# AutoTunerV3.net
KiCad netlist of a schematic drawn in EAGLE
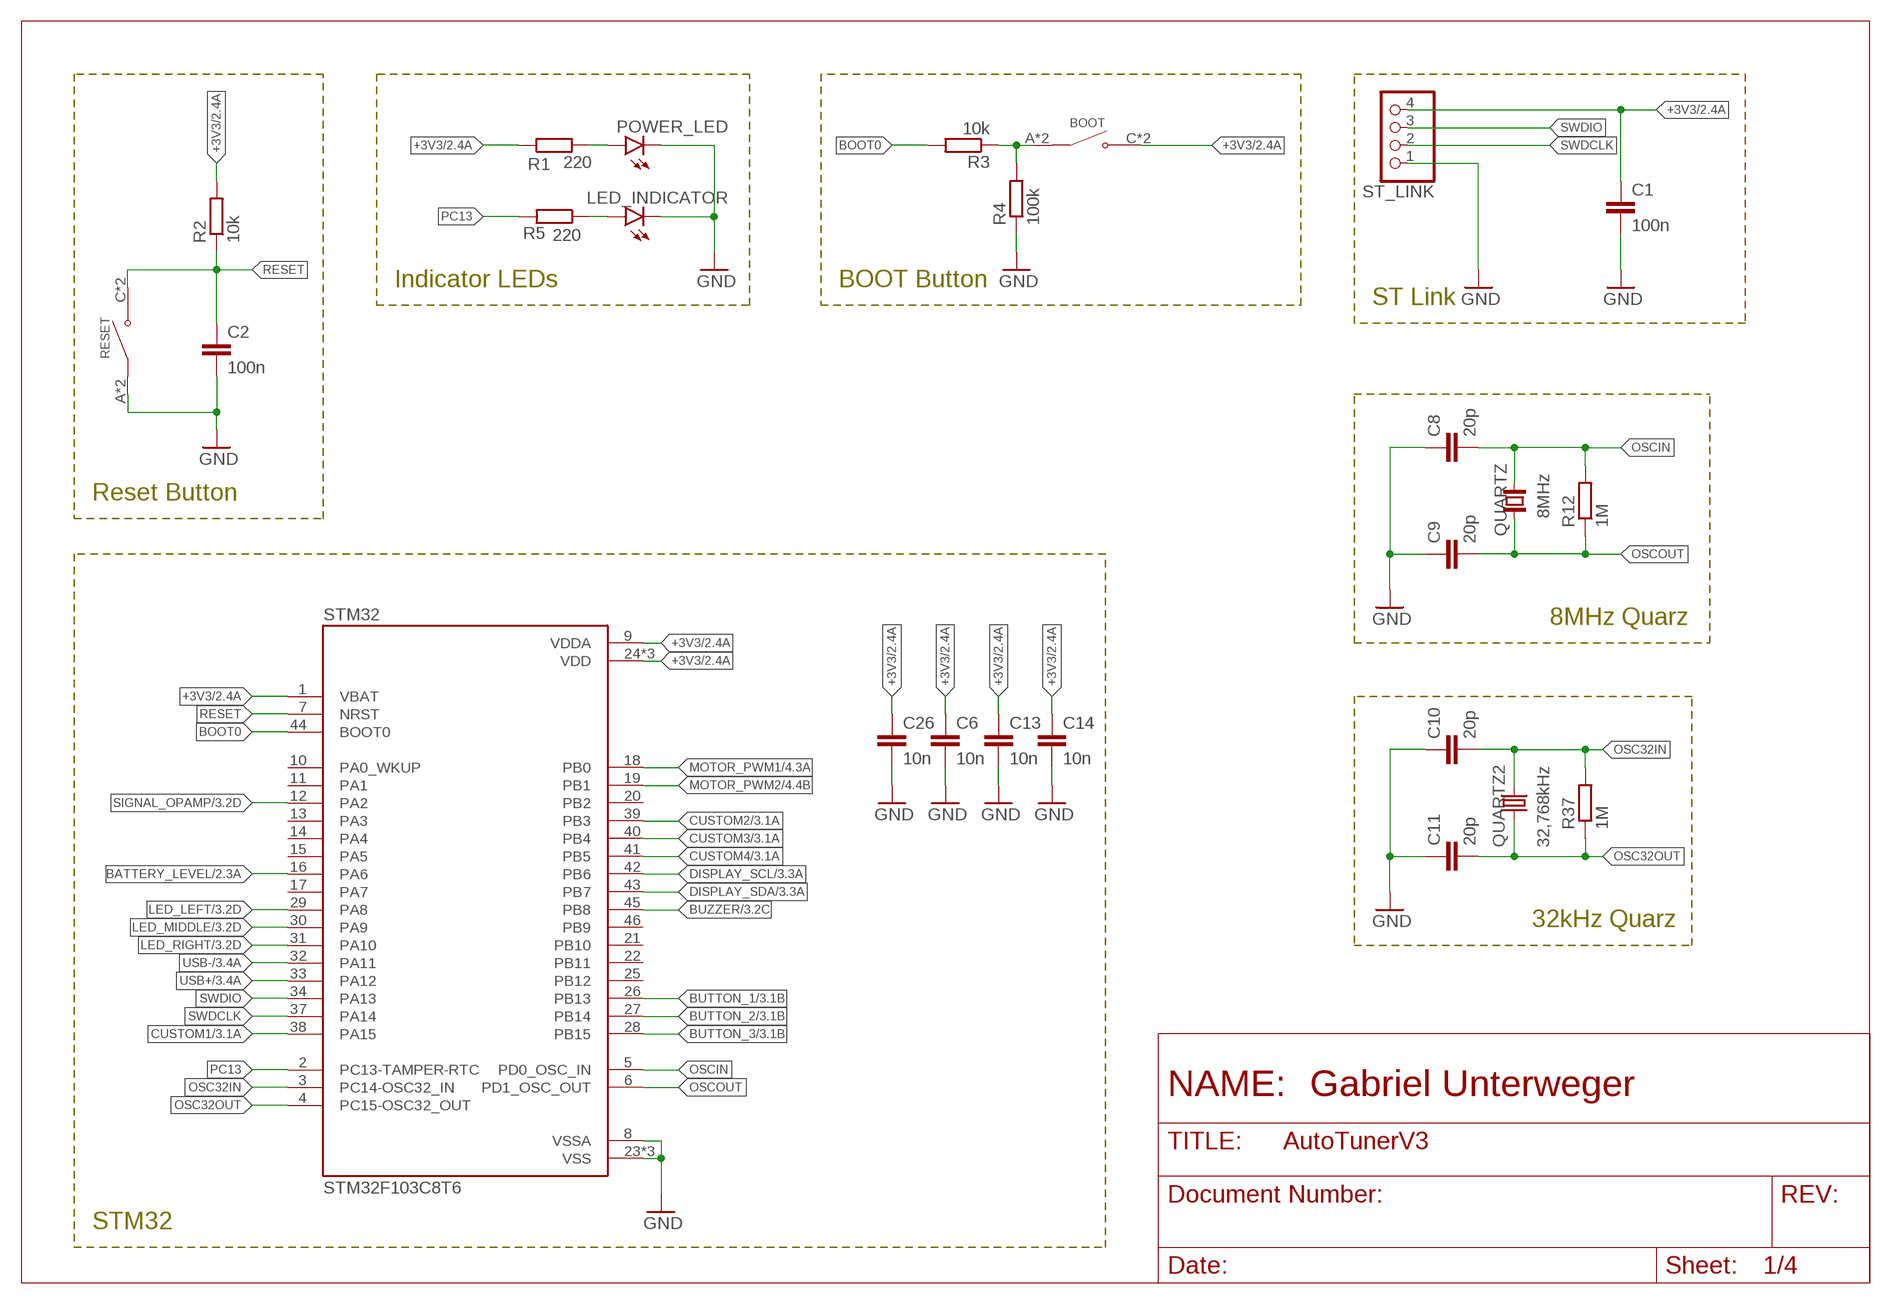
[diagram p0: schematic, sheet 1]
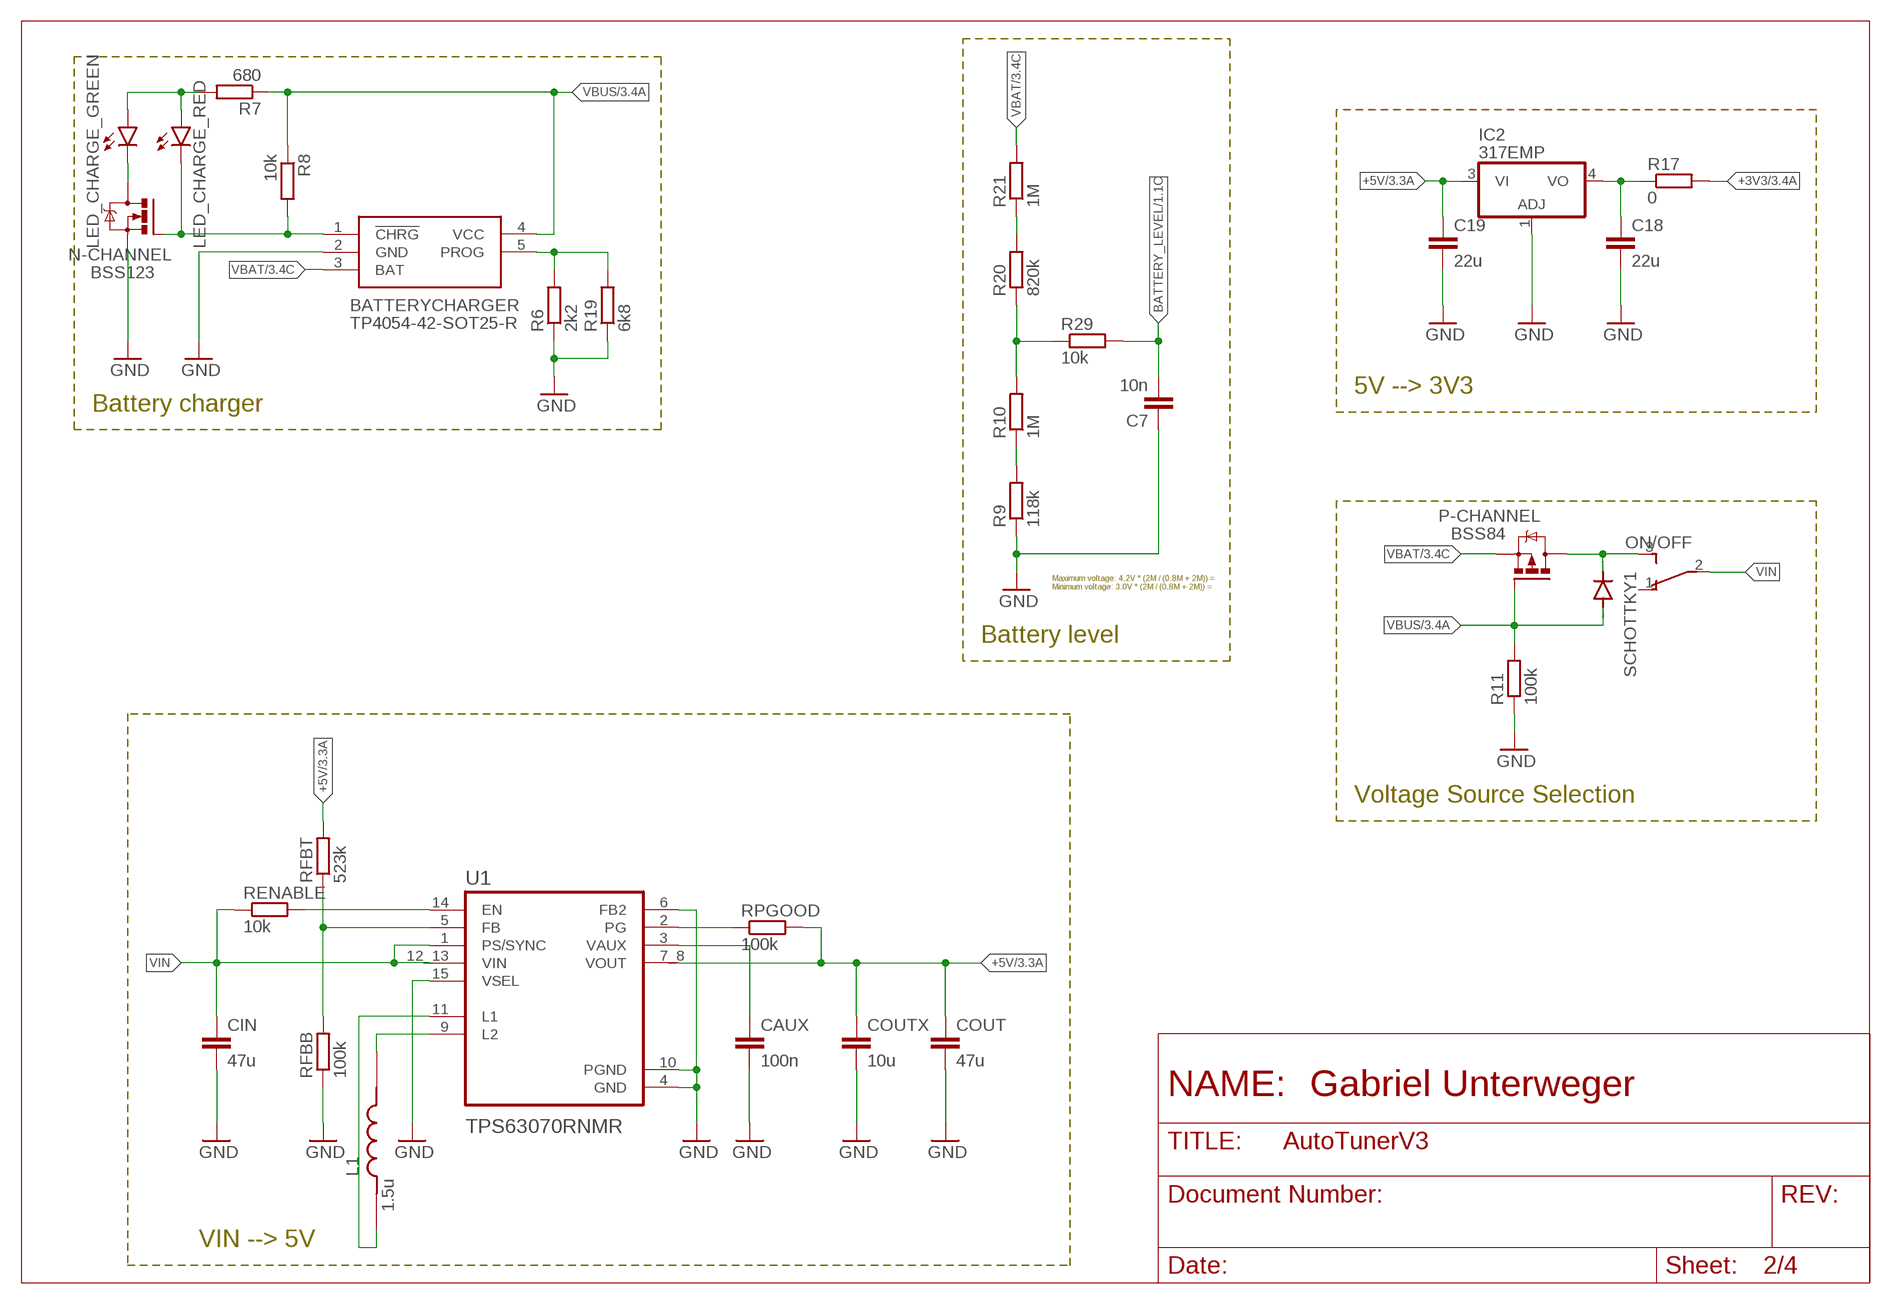
[diagram p1: schematic, sheet 2]
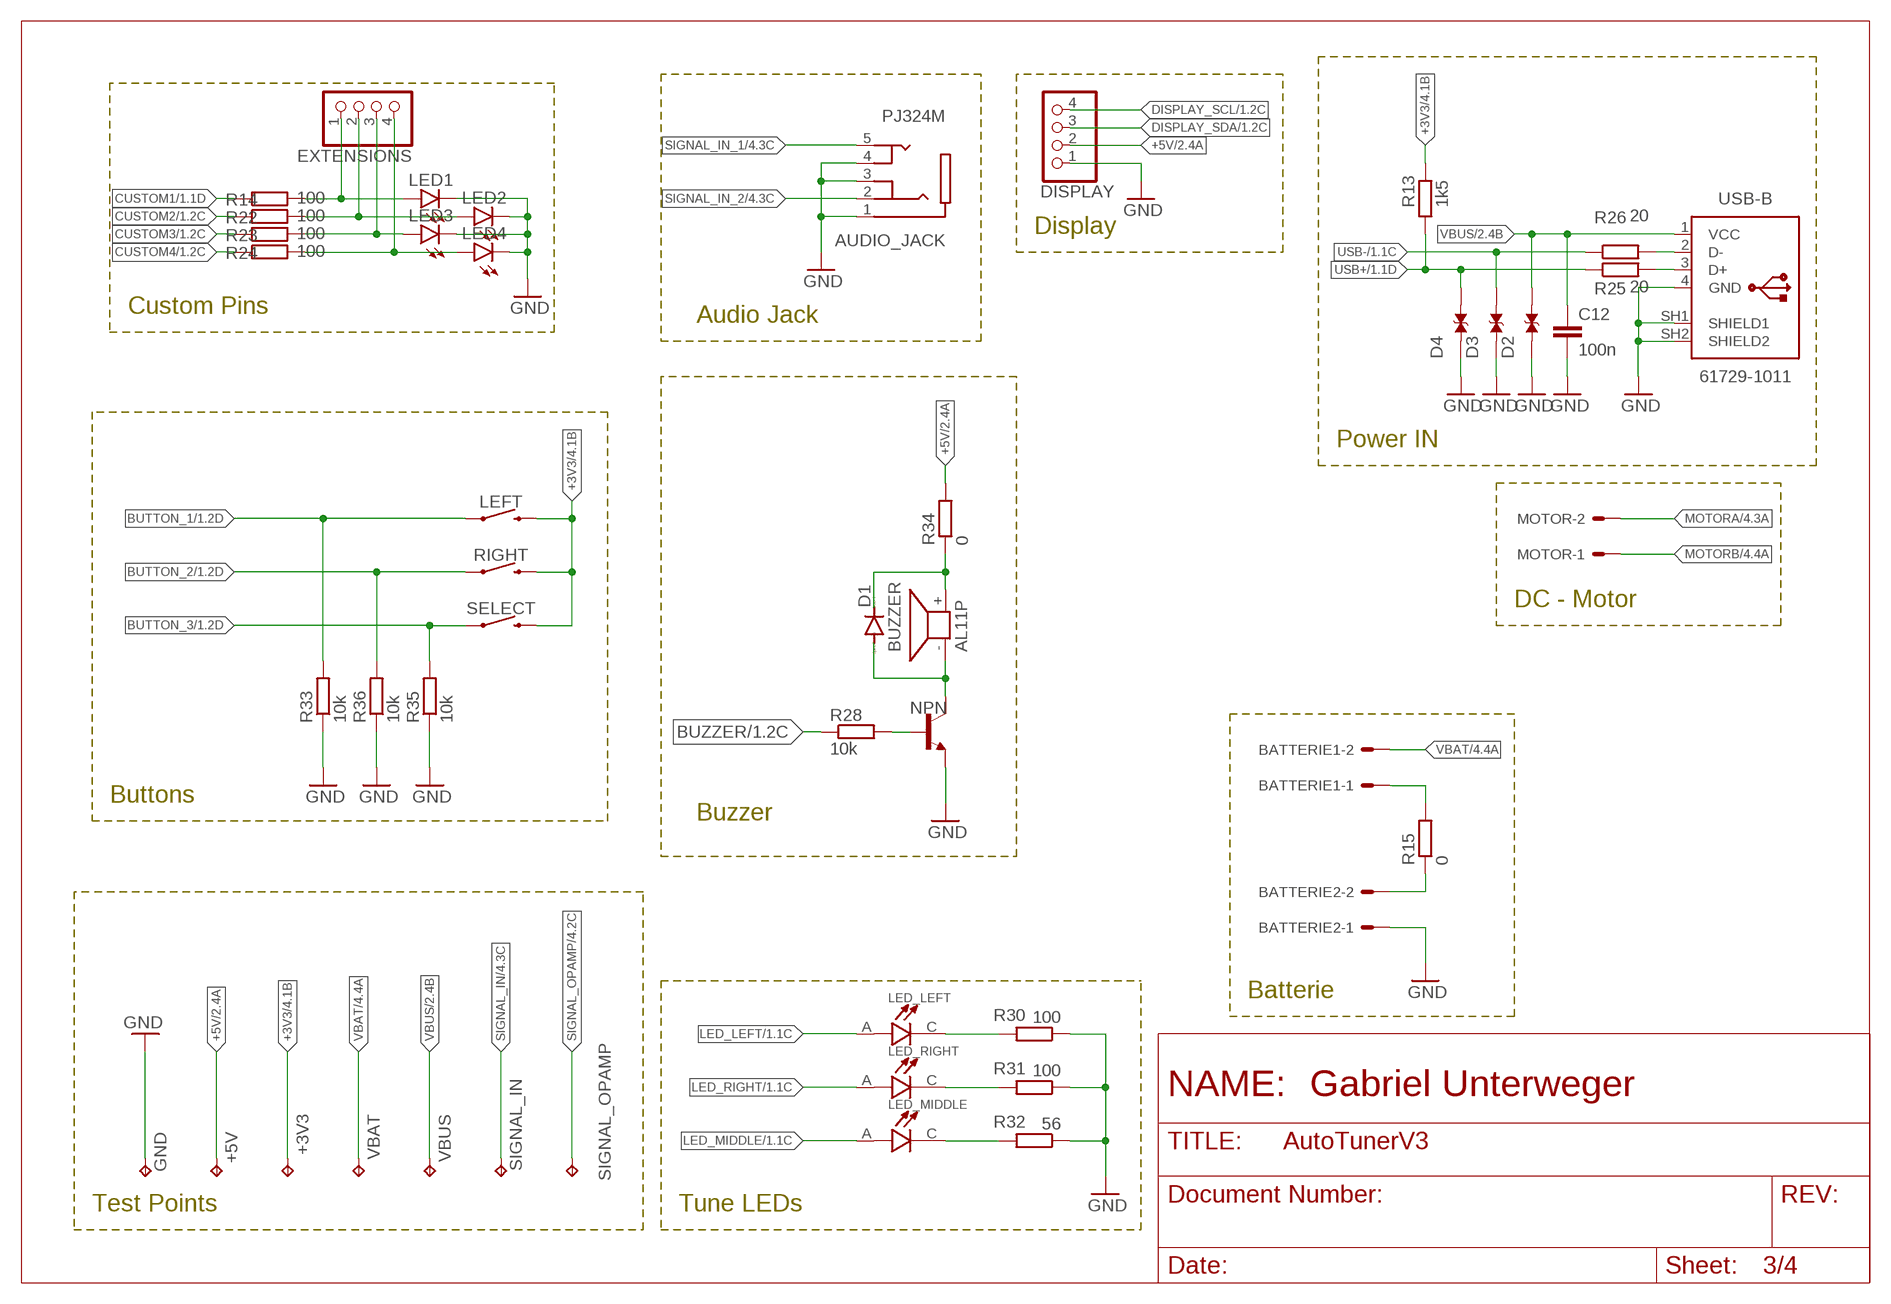
[diagram p2: schematic, sheet 3]
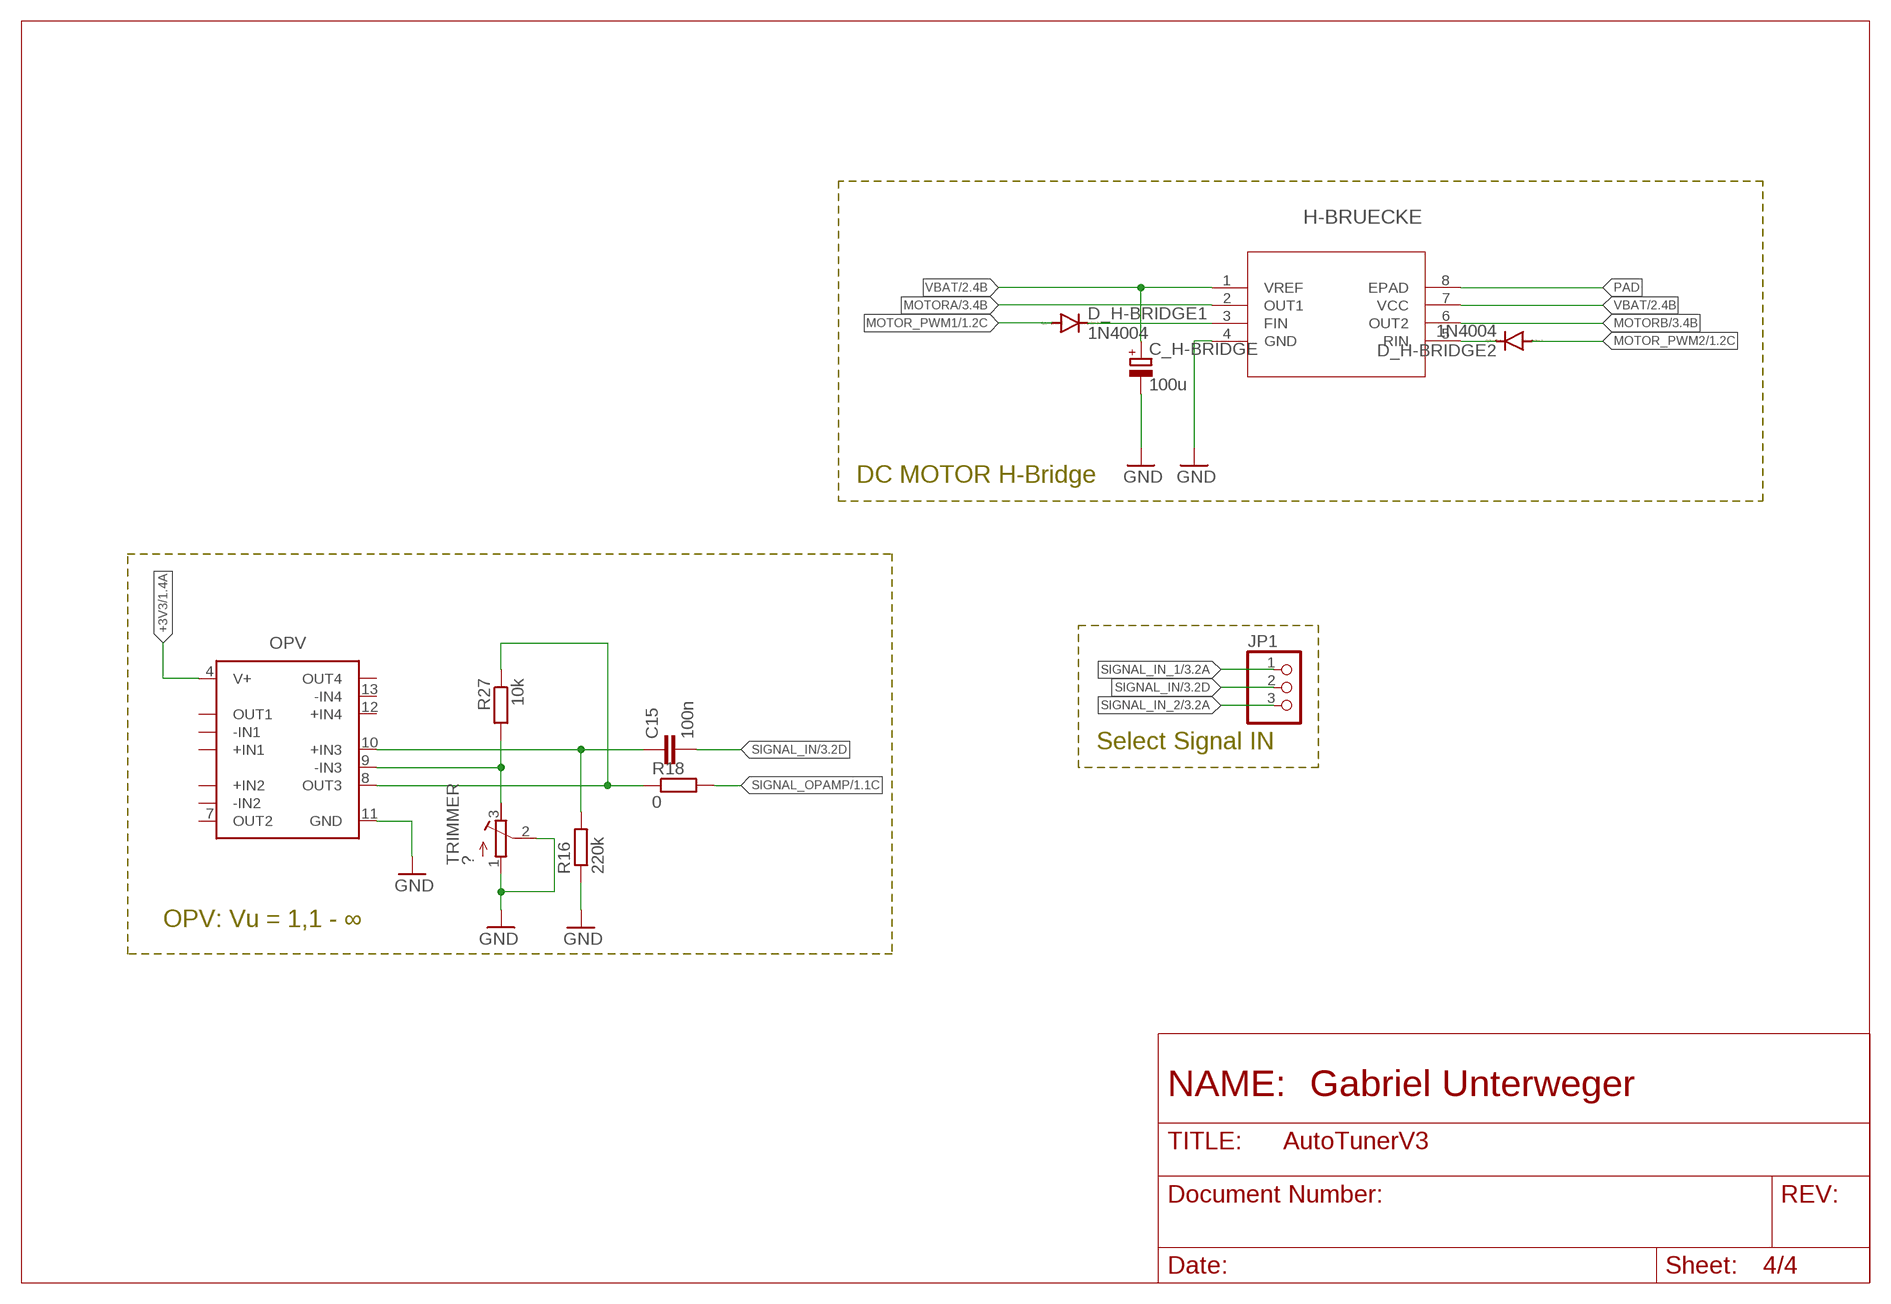
[diagram p3: schematic, sheet 4]

(export (version "E")
  (design (tool "Eeschema 10.0.6"))
  (components
    (comp (ref "+3V3")
      (value "TPB1,27")
      (footprint "eagle-import:B1,27")
      (libsource (lib "eagle-import") (part "TPB1,27"))
    )
    (comp (ref "+5V")
      (value "TPB1,27")
      (footprint "eagle-import:B1,27")
      (libsource (lib "eagle-import") (part "TPB1,27"))
    )
    (comp (ref "AUDIO_JACK")
      (value "PJ324M")
      (footprint "eagle-import:WENZHOU_PJ324M")
      (fields (field (name "MF") "Wenzhou QingPu Electronics Co.Ltd"))
      (libsource (lib "eagle-import") (part "PJ324M"))
    )
    (comp (ref "BATTERIE1")
      (value "22-27-2021-02")
      (footprint "eagle-import:6410-02")
      (fields (field (name "MF") "MOLEX"))
      (libsource (lib "eagle-import") (part "22-?-0227-2021"))
    )
    (comp (ref "BATTERIE2")
      (value "22-27-2021-02")
      (footprint "eagle-import:6410-02")
      (fields (field (name "MF") "MOLEX"))
      (libsource (lib "eagle-import") (part "22-?-0227-2021"))
    )
    (comp (ref "BUZZER")
      (value "AL11P")
      (footprint "eagle-import:AL11P")
      (libsource (lib "eagle-import") (part "AL11P"))
    )
    (comp (ref "C12")
      (value "100n")
      (footprint "eagle-import:C0805")
      (libsource (lib "eagle-import") (part "C-EUC0805"))
    )
    (comp (ref "D1")
      (value "DIODE-SOD323-R")
      (footprint "eagle-import:SOD323-R")
      (fields (field (name "LCSC_PART") "C2128"))
      (libsource (lib "eagle-import") (part "DIODE-SOD323-R"))
    )
    (comp (ref "D2")
      (value "TESD5V0L1UC_RJG")
      (footprint "eagle-import:DIO_TESD5V0L1UC_RJG")
      (fields
        (field (name "MF") "Taiwan Semiconductor Corporation")
        (field (name "MP") "TESD5V0L1UC RJG")
        (field (name "LCSC_PART") "C7420372")
      )
      (libsource (lib "eagle-import") (part "TESD5V0L1UC_RJG"))
    )
    (comp (ref "D3")
      (value "TESD5V0L1UC_RJG")
      (footprint "eagle-import:DIO_TESD5V0L1UC_RJG")
      (fields
        (field (name "MF") "Taiwan Semiconductor Corporation")
        (field (name "MP") "TESD5V0L1UC RJG")
        (field (name "LCSC_PART") "C7420372")
      )
      (libsource (lib "eagle-import") (part "TESD5V0L1UC_RJG"))
    )
    (comp (ref "D4")
      (value "TESD5V0L1UC_RJG")
      (footprint "eagle-import:DIO_TESD5V0L1UC_RJG")
      (fields
        (field (name "MF") "Taiwan Semiconductor Corporation")
        (field (name "MP") "TESD5V0L1UC RJG")
        (field (name "LCSC_PART") "C7420372")
      )
      (libsource (lib "eagle-import") (part "TESD5V0L1UC_RJG"))
    )
    (comp (ref "DISPLAY")
      (value "PINHD-1X4")
      (footprint "eagle-import:1X04")
      (libsource (lib "eagle-import") (part "PINHD-1X4"))
    )
    (comp (ref "EXTENSIONS")
      (value "PINHD-1X4/90")
      (footprint "eagle-import:1X04_90")
      (libsource (lib "eagle-import") (part "PINHD-1X4/90"))
    )
    (comp (ref "GND")
      (value "TPB1,27")
      (footprint "eagle-import:B1,27")
      (libsource (lib "eagle-import") (part "TPB1,27"))
    )
    (comp (ref "LED1")
      (value "LEDCHIP-LED0805")
      (footprint "eagle-import:CHIP-LED0805")
      (fields (field (name "LCSC_PART") "C2297"))
      (libsource (lib "eagle-import") (part "LEDCHIP-LED0805"))
    )
    (comp (ref "LED2")
      (value "LEDCHIP-LED0805")
      (footprint "eagle-import:CHIP-LED0805")
      (fields (field (name "LCSC_PART") "C2297"))
      (libsource (lib "eagle-import") (part "LEDCHIP-LED0805"))
    )
    (comp (ref "LED3")
      (value "LEDCHIP-LED0805")
      (footprint "eagle-import:CHIP-LED0805")
      (fields (field (name "LCSC_PART") "C2297"))
      (libsource (lib "eagle-import") (part "LEDCHIP-LED0805"))
    )
    (comp (ref "LED4")
      (value "LEDCHIP-LED0805")
      (footprint "eagle-import:CHIP-LED0805")
      (fields (field (name "LCSC_PART") "C2297"))
      (libsource (lib "eagle-import") (part "LEDCHIP-LED0805"))
    )
    (comp (ref "LED_LEFT")
      (value "L-53GD")
      (footprint "eagle-import:LEDRD254W50D500H1060")
      (fields (field (name "MF") "Kingbright"))
      (libsource (lib "eagle-import") (part "L-53GD"))
    )
    (comp (ref "LED_MIDDLE")
      (value "L-53GD")
      (footprint "eagle-import:LEDRD254W50D500H1060")
      (fields (field (name "MF") "Kingbright"))
      (libsource (lib "eagle-import") (part "L-53GD"))
    )
    (comp (ref "LED_RIGHT")
      (value "L-53GD")
      (footprint "eagle-import:LEDRD254W50D500H1060")
      (fields (field (name "MF") "Kingbright"))
      (libsource (lib "eagle-import") (part "L-53GD"))
    )
    (comp (ref "LEFT")
      (value "MOMENTARY-SWITCH-SPST-PTH-12MM")
      (footprint "eagle-import:TACTILE_SWITCH_PTH_12MM")
      (libsource (lib "eagle-import") (part "MOMENTARY-SWITCH-SPST-PTH-12MM"))
    )
    (comp (ref "MOTOR")
      (value "22-27-2021-02")
      (footprint "eagle-import:6410-02")
      (fields (field (name "MF") "MOLEX"))
      (libsource (lib "eagle-import") (part "22-?-0227-2021"))
    )
    (comp (ref "NPN")
      (value "-NPN-SOT23-EBC")
      (footprint "eagle-import:SOT23-EBC")
      (fields (field (name "LCSC_PART") "C364312"))
      (libsource (lib "eagle-import") (part "-NPN-SOT23-EBC"))
    )
    (comp (ref "R13")
      (value "1k5")
      (footprint "eagle-import:R0805")
      (libsource (lib "eagle-import") (part "R-EU_R0805"))
    )
    (comp (ref "R14")
      (value "100")
      (footprint "eagle-import:R0805")
      (libsource (lib "eagle-import") (part "R-EU_R0805"))
    )
    (comp (ref "R15")
      (value "0")
      (footprint "eagle-import:R0805")
      (libsource (lib "eagle-import") (part "R-EU_R0805"))
    )
    (comp (ref "R22")
      (value "100")
      (footprint "eagle-import:R0805")
      (libsource (lib "eagle-import") (part "R-EU_R0805"))
    )
    (comp (ref "R23")
      (value "100")
      (footprint "eagle-import:R0805")
      (libsource (lib "eagle-import") (part "R-EU_R0805"))
    )
    (comp (ref "R24")
      (value "100")
      (footprint "eagle-import:R0805")
      (libsource (lib "eagle-import") (part "R-EU_R0805"))
    )
    (comp (ref "R25")
      (value "20")
      (footprint "eagle-import:R0805")
      (libsource (lib "eagle-import") (part "R-EU_R0805"))
    )
    (comp (ref "R26")
      (value "20")
      (footprint "eagle-import:R0805")
      (libsource (lib "eagle-import") (part "R-EU_R0805"))
    )
    (comp (ref "R28")
      (value "10k")
      (footprint "eagle-import:R0805")
      (libsource (lib "eagle-import") (part "R-EU_R0805"))
    )
    (comp (ref "R30")
      (value "100")
      (footprint "eagle-import:R0805")
      (libsource (lib "eagle-import") (part "R-EU_R0805"))
    )
    (comp (ref "R31")
      (value "100")
      (footprint "eagle-import:R0805")
      (libsource (lib "eagle-import") (part "R-EU_R0805"))
    )
    (comp (ref "R32")
      (value "56")
      (footprint "eagle-import:R0805")
      (libsource (lib "eagle-import") (part "R-EU_R0805"))
    )
    (comp (ref "R33")
      (value "10k")
      (footprint "eagle-import:R0805")
      (libsource (lib "eagle-import") (part "R-EU_R0805"))
    )
    (comp (ref "R34")
      (value "0")
      (footprint "eagle-import:R0805")
      (libsource (lib "eagle-import") (part "R-EU_R0805"))
    )
    (comp (ref "R35")
      (value "10k")
      (footprint "eagle-import:R0805")
      (libsource (lib "eagle-import") (part "R-EU_R0805"))
    )
    (comp (ref "R36")
      (value "10k")
      (footprint "eagle-import:R0805")
      (libsource (lib "eagle-import") (part "R-EU_R0805"))
    )
    (comp (ref "RIGHT")
      (value "MOMENTARY-SWITCH-SPST-PTH-12MM")
      (footprint "eagle-import:TACTILE_SWITCH_PTH_12MM")
      (libsource (lib "eagle-import") (part "MOMENTARY-SWITCH-SPST-PTH-12MM"))
    )
    (comp (ref "SELECT")
      (value "MOMENTARY-SWITCH-SPST-PTH-12MM")
      (footprint "eagle-import:TACTILE_SWITCH_PTH_12MM")
      (libsource (lib "eagle-import") (part "MOMENTARY-SWITCH-SPST-PTH-12MM"))
    )
    (comp (ref "SIGNAL_IN")
      (value "TPB1,27")
      (footprint "eagle-import:B1,27")
      (libsource (lib "eagle-import") (part "TPB1,27"))
    )
    (comp (ref "SIGNAL_OPAMP")
      (value "TPB1,27")
      (footprint "eagle-import:B1,27")
      (libsource (lib "eagle-import") (part "TPB1,27"))
    )
    (comp (ref "USB-B")
      (value "61729-1011")
      (footprint "eagle-import:61729-1011BLF")
      (fields (field (name "MANUFACTURER") "Amphenol ICC (FCI)") (field (name "MPN") "61729-1011BLF"))
      (libsource (lib "eagle-import") (part "61729-1011"))
    )
    (comp (ref "VBAT")
      (value "TPB1,27")
      (footprint "eagle-import:B1,27")
      (libsource (lib "eagle-import") (part "TPB1,27"))
    )
    (comp (ref "VBUS")
      (value "TPB1,27")
      (footprint "eagle-import:B1,27")
      (libsource (lib "eagle-import") (part "TPB1,27"))
    )
    (comp (ref "BOOT")
      (value "TS-1187A-B-A-B")
      (footprint "eagle-import:SW_TS-1187A-B-A-B")
      (fields (field (name "MF") "XKB Industrial Precision") (field (name "LCSC_PART") "C318884"))
      (libsource (lib "eagle-import") (part "TS-1187A-B-A-B"))
    )
    (comp (ref "C1")
      (value "100n")
      (footprint "eagle-import:C0805")
      (libsource (lib "eagle-import") (part "C-EUC0805"))
    )
    (comp (ref "C2")
      (value "100n")
      (footprint "eagle-import:C0805")
      (libsource (lib "eagle-import") (part "C-EUC0805"))
    )
    (comp (ref "C6")
      (value "10n")
      (footprint "eagle-import:C0805")
      (libsource (lib "eagle-import") (part "C-EUC0805"))
    )
    (comp (ref "C8")
      (value "20p")
      (footprint "eagle-import:C0805")
      (libsource (lib "eagle-import") (part "C-EUC0805"))
    )
    (comp (ref "C9")
      (value "20p")
      (footprint "eagle-import:C0805")
      (libsource (lib "eagle-import") (part "C-EUC0805"))
    )
    (comp (ref "C10")
      (value "20p")
      (footprint "eagle-import:C0805")
      (libsource (lib "eagle-import") (part "C-EUC0805"))
    )
    (comp (ref "C11")
      (value "20p")
      (footprint "eagle-import:C0805")
      (libsource (lib "eagle-import") (part "C-EUC0805"))
    )
    (comp (ref "C13")
      (value "10n")
      (footprint "eagle-import:C0805")
      (libsource (lib "eagle-import") (part "C-EUC0805"))
    )
    (comp (ref "C14")
      (value "10n")
      (footprint "eagle-import:C0805")
      (libsource (lib "eagle-import") (part "C-EUC0805"))
    )
    (comp (ref "C26")
      (value "10n")
      (footprint "eagle-import:C0805")
      (libsource (lib "eagle-import") (part "C-EUC0805"))
    )
    (comp (ref "LED_INDICATOR")
      (value "LEDCHIPLED_0805")
      (footprint "eagle-import:CHIPLED_0805")
      (fields (field (name "LCSC_PART") "C2296"))
      (libsource (lib "eagle-import") (part "LEDCHIPLED_0805"))
    )
    (comp (ref "POWER_LED")
      (value "LEDCHIPLED_0805")
      (footprint "eagle-import:CHIPLED_0805")
      (fields (field (name "LCSC_PART") "C2297"))
      (libsource (lib "eagle-import") (part "LEDCHIPLED_0805"))
    )
    (comp (ref "QUARTZ")
      (value "8MHz")
      (footprint "eagle-import:CRYSTAL_2-SMD-5X3")
      (fields (field (name "LCSC_PART") "C115962"))
      (libsource (lib "eagle-import") (part "CRYSTAL_NX5032GA"))
    )
    (comp (ref "QUARTZ2")
      (value "32,768kHz")
      (footprint "eagle-import:3.2X1.5")
      (fields (field (name "LCSC_PART") "C32346"))
      (libsource (lib "eagle-import") (part "KX-327-NHF"))
    )
    (comp (ref "R1")
      (value "220")
      (footprint "eagle-import:R0805")
      (fields (field (name "LCSC_PART") "C17557"))
      (libsource (lib "eagle-import") (part "R-EU_R0805"))
    )
    (comp (ref "R2")
      (value "10k")
      (footprint "eagle-import:R0805")
      (libsource (lib "eagle-import") (part "R-EU_R0805"))
    )
    (comp (ref "R3")
      (value "10k")
      (footprint "eagle-import:R0805")
      (libsource (lib "eagle-import") (part "R-EU_R0805"))
    )
    (comp (ref "R4")
      (value "100k")
      (footprint "eagle-import:R0805")
      (libsource (lib "eagle-import") (part "R-EU_R0805"))
    )
    (comp (ref "R5")
      (value "220")
      (footprint "eagle-import:R0805")
      (fields (field (name "LCSC_PART") "C17802"))
      (libsource (lib "eagle-import") (part "R-EU_R0805"))
    )
    (comp (ref "R12")
      (value "1M")
      (footprint "eagle-import:R0805")
      (libsource (lib "eagle-import") (part "R-EU_R0805"))
    )
    (comp (ref "R37")
      (value "1M")
      (footprint "eagle-import:R0805")
      (libsource (lib "eagle-import") (part "R-EU_R0805"))
    )
    (comp (ref "RESET")
      (value "TS-1187A-B-A-B")
      (footprint "eagle-import:SW_TS-1187A-B-A-B")
      (fields (field (name "MF") "XKB Industrial Precision") (field (name "LCSC_PART") "C318884"))
      (libsource (lib "eagle-import") (part "TS-1187A-B-A-B"))
    )
    (comp (ref "STM32")
      (value "STM32F103C8T6")
      (footprint "eagle-import:QFP50P900X900X160-48N")
      (fields (field (name "MF") "STMicroelectronics") (field (name "LCSC_PART") "C8734"))
      (libsource (lib "eagle-import") (part "STM32F103C8T6"))
    )
    (comp (ref "ST_LINK")
      (value "PINHD-1X4/90")
      (footprint "eagle-import:1X04_90")
      (libsource (lib "eagle-import") (part "PINHD-1X4/90"))
    )
    (comp (ref "BATTERYCHARGER")
      (value "TP4054-42-SOT25-R")
      (footprint "eagle-import:SOT95P280X100-5N")
      (fields (field (name "LCSC_PART") "C32574"))
      (libsource (lib "eagle-import") (part "TP4054-42-SOT25-R"))
    )
    (comp (ref "C7")
      (value "10n")
      (footprint "eagle-import:C0805")
      (libsource (lib "eagle-import") (part "C-EUC0805"))
    )
    (comp (ref "C18")
      (value "22u")
      (footprint "eagle-import:C1206")
      (fields (field (name "LCSC_PART") "C12891"))
      (libsource (lib "eagle-import") (part "C-EUC1206"))
    )
    (comp (ref "C19")
      (value "22u")
      (footprint "eagle-import:C1206")
      (fields (field (name "LCSC_PART") "C12891"))
      (libsource (lib "eagle-import") (part "C-EUC1206"))
    )
    (comp (ref "CAUX")
      (value "100n")
      (footprint "eagle-import:C0402")
      (fields (field (name "LCSC_PART") "C1525"))
      (libsource (lib "eagle-import") (part "C-EUC0402"))
    )
    (comp (ref "CIN")
      (value "47u")
      (footprint "eagle-import:C1206")
      (fields (field (name "LCSC_PART") "C96123"))
      (libsource (lib "eagle-import") (part "C-EUC1206"))
    )
    (comp (ref "COUT")
      (value "47u")
      (footprint "eagle-import:C1206")
      (fields (field (name "LCSC_PART") "C96123"))
      (libsource (lib "eagle-import") (part "C-EUC1206"))
    )
    (comp (ref "COUTX")
      (value "10u")
      (footprint "eagle-import:C0603")
      (fields (field (name "LCSC_PART") "C19702"))
      (libsource (lib "eagle-import") (part "C-EUC0603"))
    )
    (comp (ref "IC2")
      (value "317EMP")
      (footprint "eagle-import:SOT223")
      (fields (field (name "LCSC_PART") "C6186"))
      (libsource (lib "eagle-import") (part "317EMP"))
    )
    (comp (ref "L1")
      (value "1.5u")
      (footprint "eagle-import:IND_XFL4020-152MEC")
      (fields
        (field (name "MF") "Coilcraft")
        (field (name "MP") "XFL4020-152MEC")
        (field (name "LCSC_PART") "C3033018")
      )
      (libsource (lib "eagle-import") (part "XFL4020-152MEC"))
    )
    (comp (ref "LED_CHARGE_GREEN")
      (value "LEDCHIPLED_0805")
      (footprint "eagle-import:CHIPLED_0805")
      (fields (field (name "LCSC_PART") "C2297"))
      (libsource (lib "eagle-import") (part "LEDCHIPLED_0805"))
    )
    (comp (ref "LED_CHARGE_RED")
      (value "LEDCHIPLED_0805")
      (footprint "eagle-import:CHIPLED_0805")
      (fields (field (name "LCSC_PART") "C84256"))
      (libsource (lib "eagle-import") (part "LEDCHIPLED_0805"))
    )
    (comp (ref "N-CHANNEL")
      (value "BSS123")
      (footprint "eagle-import:SOT23")
      (fields
        (field (name "MANUFACTURER") "ON Semiconductor")
        (field (name "MPN") "BSS123L")
        (field (name "LCSC_PART") "C20917")
      )
      (libsource (lib "eagle-import") (part "NMOSFET__SOT23-GSDBSS123"))
    )
    (comp (ref "ON/OFF")
      (value "TL36PO")
      (footprint "eagle-import:TL3XPO")
      (libsource (lib "eagle-import") (part "TL36PO"))
    )
    (comp (ref "P-CHANNEL")
      (value "BSS84")
      (footprint "eagle-import:SOT23")
      (fields (field (name "MANUFACTURER") "ON Semiconductor"))
      (libsource (lib "eagle-import") (part "PMOSFET__SOT23-GSDBSS84"))
    )
    (comp (ref "R6")
      (value "2k2")
      (footprint "eagle-import:R0805")
      (libsource (lib "eagle-import") (part "R-EU_R0805"))
    )
    (comp (ref "R7")
      (value "680")
      (footprint "eagle-import:R0805")
      (libsource (lib "eagle-import") (part "R-EU_R0805"))
    )
    (comp (ref "R8")
      (value "10k")
      (footprint "eagle-import:R0805")
      (libsource (lib "eagle-import") (part "R-EU_R0805"))
    )
    (comp (ref "R9")
      (value "118k")
      (footprint "eagle-import:R0805")
      (libsource (lib "eagle-import") (part "R-EU_R0805"))
    )
    (comp (ref "R10")
      (value "1M")
      (footprint "eagle-import:R0805")
      (libsource (lib "eagle-import") (part "R-EU_R0805"))
    )
    (comp (ref "R11")
      (value "100k")
      (footprint "eagle-import:R0805")
      (libsource (lib "eagle-import") (part "R-EU_R0805"))
    )
    (comp (ref "R17")
      (value "0")
      (footprint "eagle-import:R0805")
      (libsource (lib "eagle-import") (part "R-EU_R0805"))
    )
    (comp (ref "R19")
      (value "6k8")
      (footprint "eagle-import:R0805")
      (libsource (lib "eagle-import") (part "R-EU_R0805"))
    )
    (comp (ref "R20")
      (value "820k")
      (footprint "eagle-import:R0805")
      (libsource (lib "eagle-import") (part "R-EU_R0805"))
    )
    (comp (ref "R21")
      (value "1M")
      (footprint "eagle-import:R0805")
      (libsource (lib "eagle-import") (part "R-EU_R0805"))
    )
    (comp (ref "R29")
      (value "10k")
      (footprint "eagle-import:R0805")
      (libsource (lib "eagle-import") (part "R-EU_R0805"))
    )
    (comp (ref "RENABLE")
      (value "10k")
      (footprint "eagle-import:R0805")
      (libsource (lib "eagle-import") (part "R-EU_R0805"))
    )
    (comp (ref "RFBB")
      (value "100k")
      (footprint "eagle-import:R0805")
      (libsource (lib "eagle-import") (part "R-EU_R0805"))
    )
    (comp (ref "RFBT")
      (value "523k")
      (footprint "eagle-import:R0805")
      (libsource (lib "eagle-import") (part "R-EU_R0805"))
    )
    (comp (ref "RPGOOD")
      (value "100k")
      (footprint "eagle-import:R0805")
      (libsource (lib "eagle-import") (part "R-EU_R0805"))
    )
    (comp (ref "SCHOTTKY1")
      (value "DIODE-SOD323-R")
      (footprint "eagle-import:SOD323-R")
      (fields (field (name "LCSC_PART") "C191023"))
      (libsource (lib "eagle-import") (part "DIODE-SOD323-R"))
    )
    (comp (ref "U1")
      (value "TPS63070RNMR")
      (footprint "eagle-import:VREG_TPS63070RNMR")
      (fields (field (name "MF") "Texas Instruments") (field (name "LCSC_PART") "C109322"))
      (libsource (lib "eagle-import") (part "TPS63070RNMR"))
    )
    (comp (ref "C15")
      (value "100n")
      (footprint "eagle-import:C0805")
      (libsource (lib "eagle-import") (part "C-EUC0805"))
    )
    (comp (ref "C_H-BRIDGE")
      (value "100u")
      (footprint "eagle-import:E2,5-6E")
      (libsource (lib "eagle-import") (part "CPOL-EUE2,5-6E"))
    )
    (comp (ref "D_H-BRIDGE1")
      (value "1N4004")
      (footprint "eagle-import:DO41-10")
      (libsource (lib "eagle-import") (part "1N4004"))
    )
    (comp (ref "D_H-BRIDGE2")
      (value "1N4004")
      (footprint "eagle-import:DO41-10")
      (libsource (lib "eagle-import") (part "1N4004"))
    )
    (comp (ref "H-BRUECKE")
      (value "BD6222HFP-TRHRP7_ROM-M")
      (footprint "eagle-import:HRP7_ROM-M")
      (fields
        (field (name "MANUFACTURER_PART_NUMBER") "BD6222HFP-TR")
        (field (name "COPYRIGHT") "Copyright (C) 2022 Ultra Librarian. All rights reserved.")
      )
      (libsource (lib "eagle-import") (part "BD6222HFP-TRHRP7_ROM-M"))
    )
    (comp (ref "JP1")
      (value "PINHD-1X3")
      (footprint "eagle-import:1X03")
      (libsource (lib "eagle-import") (part "PINHD-1X3"))
    )
    (comp (ref "OPV")
      (value "LM324_SOIC")
      (footprint "eagle-import:SOIC127P600X175-14N")
      (fields (field (name "MANUFACTURER") "Generic") (field (name "LCSC_PART") "C71035"))
      (libsource (lib "eagle-import") (part "LM324_SOIC"))
    )
    (comp (ref "R16")
      (value "220k")
      (footprint "eagle-import:R0805")
      (libsource (lib "eagle-import") (part "R-EU_R0805"))
    )
    (comp (ref "R18")
      (value "0")
      (footprint "eagle-import:R0805")
      (libsource (lib "eagle-import") (part "R-EU_R0805"))
    )
    (comp (ref "R27")
      (value "10k")
      (footprint "eagle-import:R0805")
      (libsource (lib "eagle-import") (part "R-EU_R0805"))
    )
    (comp (ref "TRIMMER")
      (value "?")
      (footprint "eagle-import:RTRIM3339P")
      (libsource (lib "eagle-import") (part "R-TRIMM3339P"))
    )
  )
  (nets
    (net (code "1") (name "+3V3") (class "Default")
      (node (ref "+3V3") (pin "TP") (pinfunction "TP_TP") (pintype "input"))
      (node (ref "BOOT") (pin "C") (pinfunction "NO_C") (pintype "passive"))
      (node (ref "BOOT") (pin "D") (pinfunction "NO_D") (pintype "passive"))
      (node (ref "C1") (pin "1") (pinfunction "1_1") (pintype "passive"))
      (node (ref "C13") (pin "1") (pinfunction "1_1") (pintype "passive"))
      (node (ref "C14") (pin "1") (pinfunction "1_1") (pintype "passive"))
      (node (ref "C26") (pin "1") (pinfunction "1_1") (pintype "passive"))
      (node (ref "C6") (pin "1") (pinfunction "1_1") (pintype "passive"))
      (node (ref "LEFT") (pin "3") (pinfunction "2_3") (pintype "passive"))
      (node (ref "OPV") (pin "4") (pinfunction "V+_4") (pintype "passive"))
      (node (ref "R1") (pin "1") (pinfunction "1_1") (pintype "passive"))
      (node (ref "R13") (pin "2") (pinfunction "2_2") (pintype "passive"))
      (node (ref "R17") (pin "2") (pinfunction "2_2") (pintype "passive"))
      (node (ref "R2") (pin "2") (pinfunction "2_2") (pintype "passive"))
      (node (ref "RIGHT") (pin "3") (pinfunction "2_3") (pintype "passive"))
      (node (ref "SELECT") (pin "3") (pinfunction "2_3") (pintype "passive"))
      (node (ref "STM32") (pin "1") (pinfunction "VBAT_1") (pintype "bidirectional"))
      (node (ref "STM32") (pin "24") (pinfunction "VDD_24") (pintype "power_in"))
      (node (ref "STM32") (pin "36") (pinfunction "VDD_36") (pintype "power_in"))
      (node (ref "STM32") (pin "48") (pinfunction "VDD_48") (pintype "power_in"))
      (node (ref "STM32") (pin "9") (pinfunction "VDDA_9") (pintype "power_in"))
      (node (ref "ST_LINK") (pin "4") (pinfunction "4_4") (pintype "passive"))
    )
    (net (code "2") (name "+5V") (class "Default")
      (node (ref "+5V") (pin "TP") (pinfunction "TP_TP") (pintype "input"))
      (node (ref "C19") (pin "1") (pinfunction "1_1") (pintype "passive"))
      (node (ref "COUT") (pin "1") (pinfunction "1_1") (pintype "passive"))
      (node (ref "COUTX") (pin "1") (pinfunction "1_1") (pintype "passive"))
      (node (ref "DISPLAY") (pin "2") (pinfunction "2_2") (pintype "passive"))
      (node (ref "IC2") (pin "3") (pinfunction "VI_3") (pintype "input"))
      (node (ref "R34") (pin "2") (pinfunction "2_2") (pintype "passive"))
      (node (ref "RFBT") (pin "2") (pinfunction "2_2") (pintype "passive"))
      (node (ref "RPGOOD") (pin "2") (pinfunction "2_2") (pintype "passive"))
      (node (ref "U1") (pin "7_8") (pinfunction "VOUT_7_8") (pintype "output"))
    )
    (net (code "3") (name "BATTERY_LEVEL") (class "Default")
      (node (ref "C7") (pin "2") (pinfunction "2_2") (pintype "passive"))
      (node (ref "R29") (pin "2") (pinfunction "2_2") (pintype "passive"))
      (node (ref "STM32") (pin "16") (pinfunction "PA6_16") (pintype "bidirectional"))
    )
    (net (code "4") (name "BOOT0") (class "Default")
      (node (ref "R3") (pin "2") (pinfunction "2_2") (pintype "passive"))
      (node (ref "STM32") (pin "44") (pinfunction "BOOT0_44") (pintype "input"))
    )
    (net (code "5") (name "BUTTON_1") (class "Default")
      (node (ref "LEFT") (pin "1") (pinfunction "1_1") (pintype "passive"))
      (node (ref "R33") (pin "2") (pinfunction "2_2") (pintype "passive"))
      (node (ref "STM32") (pin "26") (pinfunction "PB13_26") (pintype "bidirectional"))
    )
    (net (code "6") (name "BUTTON_2") (class "Default")
      (node (ref "R36") (pin "2") (pinfunction "2_2") (pintype "passive"))
      (node (ref "RIGHT") (pin "1") (pinfunction "1_1") (pintype "passive"))
      (node (ref "STM32") (pin "27") (pinfunction "PB14_27") (pintype "bidirectional"))
    )
    (net (code "7") (name "BUTTON_3") (class "Default")
      (node (ref "R35") (pin "2") (pinfunction "2_2") (pintype "passive"))
      (node (ref "SELECT") (pin "1") (pinfunction "1_1") (pintype "passive"))
      (node (ref "STM32") (pin "28") (pinfunction "PB15_28") (pintype "bidirectional"))
    )
    (net (code "8") (name "BUZZER") (class "Default")
      (node (ref "R28") (pin "1") (pinfunction "1_1") (pintype "passive"))
      (node (ref "STM32") (pin "45") (pinfunction "PB8_45") (pintype "bidirectional"))
    )
    (net (code "9") (name "CUSTOM1") (class "Default")
      (node (ref "R14") (pin "1") (pinfunction "1_1") (pintype "passive"))
      (node (ref "STM32") (pin "38") (pinfunction "PA15_38") (pintype "bidirectional"))
    )
    (net (code "10") (name "CUSTOM2") (class "Default")
      (node (ref "R22") (pin "1") (pinfunction "1_1") (pintype "passive"))
      (node (ref "STM32") (pin "39") (pinfunction "PB3_39") (pintype "bidirectional"))
    )
    (net (code "11") (name "CUSTOM3") (class "Default")
      (node (ref "R23") (pin "1") (pinfunction "1_1") (pintype "passive"))
      (node (ref "STM32") (pin "40") (pinfunction "PB4_40") (pintype "bidirectional"))
    )
    (net (code "12") (name "CUSTOM4") (class "Default")
      (node (ref "R24") (pin "1") (pinfunction "1_1") (pintype "passive"))
      (node (ref "STM32") (pin "41") (pinfunction "PB5_41") (pintype "bidirectional"))
    )
    (net (code "13") (name "DISPLAY_SCL") (class "Default")
      (node (ref "DISPLAY") (pin "4") (pinfunction "4_4") (pintype "passive"))
      (node (ref "STM32") (pin "42") (pinfunction "PB6_42") (pintype "bidirectional"))
    )
    (net (code "14") (name "DISPLAY_SDA") (class "Default")
      (node (ref "DISPLAY") (pin "3") (pinfunction "3_3") (pintype "passive"))
      (node (ref "STM32") (pin "43") (pinfunction "PB7_43") (pintype "bidirectional"))
    )
    (net (code "15") (name "GND") (class "Default")
      (node (ref "AUDIO_JACK") (pin "1") (pinfunction "SLEEVE_1") (pintype "passive"))
      (node (ref "AUDIO_JACK") (pin "3") (pinfunction "RING_2_3") (pintype "passive"))
      (node (ref "AUDIO_JACK") (pin "4") (pinfunction "TIP_1_4") (pintype "passive"))
      (node (ref "BATTERIE2") (pin "1") (pinfunction "S_1") (pintype "passive"))
      (node (ref "BATTERYCHARGER") (pin "2") (pinfunction "GND_2") (pintype "bidirectional"))
      (node (ref "C1") (pin "2") (pinfunction "2_2") (pintype "passive"))
      (node (ref "C10") (pin "1") (pinfunction "1_1") (pintype "passive"))
      (node (ref "C11") (pin "1") (pinfunction "1_1") (pintype "passive"))
      (node (ref "C12") (pin "2") (pinfunction "2_2") (pintype "passive"))
      (node (ref "C13") (pin "2") (pinfunction "2_2") (pintype "passive"))
      (node (ref "C14") (pin "2") (pinfunction "2_2") (pintype "passive"))
      (node (ref "C18") (pin "2") (pinfunction "2_2") (pintype "passive"))
      (node (ref "C19") (pin "2") (pinfunction "2_2") (pintype "passive"))
      (node (ref "C2") (pin "2") (pinfunction "2_2") (pintype "passive"))
      (node (ref "C26") (pin "2") (pinfunction "2_2") (pintype "passive"))
      (node (ref "C6") (pin "2") (pinfunction "2_2") (pintype "passive"))
      (node (ref "C7") (pin "1") (pinfunction "1_1") (pintype "passive"))
      (node (ref "C8") (pin "1") (pinfunction "1_1") (pintype "passive"))
      (node (ref "C9") (pin "1") (pinfunction "1_1") (pintype "passive"))
      (node (ref "CAUX") (pin "2") (pinfunction "2_2") (pintype "passive"))
      (node (ref "CIN") (pin "2") (pinfunction "2_2") (pintype "passive"))
      (node (ref "COUT") (pin "2") (pinfunction "2_2") (pintype "passive"))
      (node (ref "COUTX") (pin "2") (pinfunction "2_2") (pintype "passive"))
      (node (ref "C_H-BRIDGE") (pin "-") (pinfunction "-_-") (pintype "passive"))
      (node (ref "D2") (pin "1") (pinfunction "1_1") (pintype "passive"))
      (node (ref "D3") (pin "1") (pinfunction "1_1") (pintype "passive"))
      (node (ref "D4") (pin "1") (pinfunction "1_1") (pintype "passive"))
      (node (ref "DISPLAY") (pin "1") (pinfunction "1_1") (pintype "passive"))
      (node (ref "GND") (pin "TP") (pinfunction "TP_TP") (pintype "input"))
      (node (ref "H-BRUECKE") (pin "4") (pinfunction "GND_4") (pintype "passive"))
      (node (ref "IC2") (pin "1") (pinfunction "ADJ_1") (pintype "input"))
      (node (ref "LED1") (pin "C") (pinfunction "C_C") (pintype "passive"))
      (node (ref "LED2") (pin "C") (pinfunction "C_C") (pintype "passive"))
      (node (ref "LED3") (pin "C") (pinfunction "C_C") (pintype "passive"))
      (node (ref "LED4") (pin "C") (pinfunction "C_C") (pintype "passive"))
      (node (ref "LED_INDICATOR") (pin "C") (pinfunction "C_C") (pintype "passive"))
      (node (ref "N-CHANNEL") (pin "2") (pinfunction "S_2") (pintype "passive"))
      (node (ref "NPN") (pin "E") (pinfunction "E_E") (pintype "passive"))
      (node (ref "OPV") (pin "11") (pinfunction "GND_11") (pintype "passive"))
      (node (ref "POWER_LED") (pin "C") (pinfunction "C_C") (pintype "passive"))
      (node (ref "R11") (pin "1") (pinfunction "1_1") (pintype "passive"))
      (node (ref "R16") (pin "1") (pinfunction "1_1") (pintype "passive"))
      (node (ref "R19") (pin "1") (pinfunction "1_1") (pintype "passive"))
      (node (ref "R30") (pin "1") (pinfunction "1_1") (pintype "passive"))
      (node (ref "R31") (pin "1") (pinfunction "1_1") (pintype "passive"))
      (node (ref "R32") (pin "1") (pinfunction "1_1") (pintype "passive"))
      (node (ref "R33") (pin "1") (pinfunction "1_1") (pintype "passive"))
      (node (ref "R35") (pin "1") (pinfunction "1_1") (pintype "passive"))
      (node (ref "R36") (pin "1") (pinfunction "1_1") (pintype "passive"))
      (node (ref "R4") (pin "1") (pinfunction "1_1") (pintype "passive"))
      (node (ref "R6") (pin "1") (pinfunction "1_1") (pintype "passive"))
      (node (ref "R9") (pin "1") (pinfunction "1_1") (pintype "passive"))
      (node (ref "RESET") (pin "A") (pinfunction "COM_A") (pintype "passive"))
      (node (ref "RESET") (pin "B") (pinfunction "COM_B") (pintype "passive"))
      (node (ref "RFBB") (pin "1") (pinfunction "1_1") (pintype "passive"))
      (node (ref "STM32") (pin "23") (pinfunction "VSS_23") (pintype "power_in"))
      (node (ref "STM32") (pin "35") (pinfunction "VSS_35") (pintype "power_in"))
      (node (ref "STM32") (pin "47") (pinfunction "VSS_47") (pintype "power_in"))
      (node (ref "STM32") (pin "8") (pinfunction "VSSA_8") (pintype "power_in"))
      (node (ref "ST_LINK") (pin "1") (pinfunction "1_1") (pintype "passive"))
      (node (ref "TRIMMER") (pin "1") (pinfunction "A_1") (pintype "passive"))
      (node (ref "TRIMMER") (pin "2") (pinfunction "S_2") (pintype "passive"))
      (node (ref "U1") (pin "10") (pinfunction "PGND_10") (pintype "power_in"))
      (node (ref "U1") (pin "15") (pinfunction "VSEL_15") (pintype "input"))
      (node (ref "U1") (pin "4") (pinfunction "GND_4") (pintype "power_in"))
      (node (ref "U1") (pin "6") (pinfunction "FB2_6") (pintype "output"))
      (node (ref "USB-B") (pin "4") (pinfunction "GND_4") (pintype "power_in"))
      (node (ref "USB-B") (pin "SH1") (pinfunction "SHIELD1_SH1") (pintype "power_in"))
      (node (ref "USB-B") (pin "SH2") (pinfunction "SHIELD2_SH2") (pintype "power_in"))
    )
    (net (code "16") (name "LED_LEFT") (class "Default")
      (node (ref "LED_LEFT") (pin "A") (pinfunction "A_A") (pintype "passive"))
      (node (ref "STM32") (pin "29") (pinfunction "PA8_29") (pintype "bidirectional"))
    )
    (net (code "17") (name "LED_MIDDLE") (class "Default")
      (node (ref "LED_MIDDLE") (pin "A") (pinfunction "A_A") (pintype "passive"))
      (node (ref "STM32") (pin "30") (pinfunction "PA9_30") (pintype "bidirectional"))
    )
    (net (code "18") (name "LED_RIGHT") (class "Default")
      (node (ref "LED_RIGHT") (pin "A") (pinfunction "A_A") (pintype "passive"))
      (node (ref "STM32") (pin "31") (pinfunction "PA10_31") (pintype "bidirectional"))
    )
    (net (code "19") (name "MOTORA") (class "Default")
      (node (ref "H-BRUECKE") (pin "2") (pinfunction "OUT1_2") (pintype "output"))
      (node (ref "MOTOR") (pin "2") (pinfunction "S_2") (pintype "passive"))
    )
    (net (code "20") (name "MOTORB") (class "Default")
      (node (ref "H-BRUECKE") (pin "6") (pinfunction "OUT2_6") (pintype "output"))
      (node (ref "MOTOR") (pin "1") (pinfunction "S_1") (pintype "passive"))
    )
    (net (code "21") (name "MOTOR_PWM1") (class "Default")
      (node (ref "D_H-BRIDGE1") (pin "A") (pinfunction "A_A") (pintype "passive"))
      (node (ref "STM32") (pin "18") (pinfunction "PB0_18") (pintype "bidirectional"))
    )
    (net (code "22") (name "MOTOR_PWM2") (class "Default")
      (node (ref "D_H-BRIDGE2") (pin "A") (pinfunction "A_A") (pintype "passive"))
      (node (ref "STM32") (pin "19") (pinfunction "PB1_19") (pintype "bidirectional"))
    )
    (net (code "23") (name "Net-(BATTERIE1A-S)") (class "Default")
      (node (ref "BATTERIE1") (pin "1") (pinfunction "S_1") (pintype "passive"))
      (node (ref "R15") (pin "2") (pinfunction "2_2") (pintype "passive"))
    )
    (net (code "24") (name "Net-(BATTERIE2B-S)") (class "Default")
      (node (ref "BATTERIE2") (pin "2") (pinfunction "S_2") (pintype "passive"))
      (node (ref "R15") (pin "1") (pinfunction "1_1") (pintype "passive"))
    )
    (net (code "25") (name "Net-(BATTERYCHARGER-PROG)") (class "Default")
      (node (ref "BATTERYCHARGER") (pin "5") (pinfunction "PROG_5") (pintype "bidirectional"))
      (node (ref "R19") (pin "2") (pinfunction "2_2") (pintype "passive"))
      (node (ref "R6") (pin "2") (pinfunction "2_2") (pintype "passive"))
    )
    (net (code "26") (name "Net-(BATTERYCHARGER-~{CHRG})") (class "Default")
      (node (ref "BATTERYCHARGER") (pin "1") (pinfunction "~{CHRG}_1") (pintype "bidirectional"))
      (node (ref "LED_CHARGE_RED") (pin "C") (pinfunction "C_C") (pintype "passive"))
      (node (ref "N-CHANNEL") (pin "1") (pinfunction "G_1") (pintype "passive"))
      (node (ref "R8") (pin "2") (pinfunction "2_2") (pintype "passive"))
    )
    (net (code "27") (name "Net-(BOOT-COM-PadA)") (class "Default")
      (node (ref "BOOT") (pin "A") (pinfunction "COM_A") (pintype "passive"))
      (node (ref "BOOT") (pin "B") (pinfunction "COM_B") (pintype "passive"))
      (node (ref "R3") (pin "1") (pinfunction "1_1") (pintype "passive"))
      (node (ref "R4") (pin "2") (pinfunction "2_2") (pintype "passive"))
    )
    (net (code "28") (name "Net-(BUZZER-1)") (class "Default")
      (node (ref "BUZZER") (pin "-") (pinfunction "1_-") (pintype "passive"))
      (node (ref "D1") (pin "A") (pinfunction "A_A") (pintype "passive"))
      (node (ref "NPN") (pin "C") (pinfunction "C_C") (pintype "passive"))
    )
    (net (code "29") (name "Net-(BUZZER-2)") (class "Default")
      (node (ref "BUZZER") (pin "+") (pinfunction "2_+") (pintype "passive"))
      (node (ref "D1") (pin "C") (pinfunction "C_C") (pintype "passive"))
      (node (ref "R34") (pin "1") (pinfunction "1_1") (pintype "passive"))
    )
    (net (code "30") (name "Net-(EXTENSIONS-Pad1)") (class "Default")
      (node (ref "EXTENSIONS") (pin "1") (pinfunction "1_1") (pintype "passive"))
      (node (ref "LED1") (pin "A") (pinfunction "A_A") (pintype "passive"))
      (node (ref "R14") (pin "2") (pinfunction "2_2") (pintype "passive"))
    )
    (net (code "31") (name "Net-(EXTENSIONS-Pad2)") (class "Default")
      (node (ref "EXTENSIONS") (pin "2") (pinfunction "2_2") (pintype "passive"))
      (node (ref "LED2") (pin "A") (pinfunction "A_A") (pintype "passive"))
      (node (ref "R22") (pin "2") (pinfunction "2_2") (pintype "passive"))
    )
    (net (code "32") (name "Net-(EXTENSIONS-Pad3)") (class "Default")
      (node (ref "EXTENSIONS") (pin "3") (pinfunction "3_3") (pintype "passive"))
      (node (ref "LED3") (pin "A") (pinfunction "A_A") (pintype "passive"))
      (node (ref "R23") (pin "2") (pinfunction "2_2") (pintype "passive"))
    )
    (net (code "33") (name "Net-(EXTENSIONS-Pad4)") (class "Default")
      (node (ref "EXTENSIONS") (pin "4") (pinfunction "4_4") (pintype "passive"))
      (node (ref "LED4") (pin "A") (pinfunction "A_A") (pintype "passive"))
      (node (ref "R24") (pin "2") (pinfunction "2_2") (pintype "passive"))
    )
    (net (code "34") (name "Net-(H-BRUECKE-FIN)") (class "Default")
      (node (ref "D_H-BRIDGE1") (pin "C") (pinfunction "C_C") (pintype "passive"))
      (node (ref "H-BRUECKE") (pin "3") (pinfunction "FIN_3") (pintype "passive"))
    )
    (net (code "35") (name "Net-(H-BRUECKE-RIN)") (class "Default")
      (node (ref "D_H-BRIDGE2") (pin "C") (pinfunction "C_C") (pintype "passive"))
      (node (ref "H-BRUECKE") (pin "5") (pinfunction "RIN_5") (pintype "passive"))
    )
    (net (code "36") (name "Net-(IC2-VO)") (class "Default")
      (node (ref "C18") (pin "1") (pinfunction "1_1") (pintype "passive"))
      (node (ref "IC2") (pin "4") (pinfunction "VO_4") (pintype "passive"))
      (node (ref "R17") (pin "1") (pinfunction "1_1") (pintype "passive"))
    )
    (net (code "37") (name "Net-(LED_CHARGE_GREEN-PadA)") (class "Default")
      (node (ref "LED_CHARGE_GREEN") (pin "A") (pinfunction "A_A") (pintype "passive"))
      (node (ref "LED_CHARGE_RED") (pin "A") (pinfunction "A_A") (pintype "passive"))
      (node (ref "R7") (pin "2") (pinfunction "2_2") (pintype "passive"))
    )
    (net (code "38") (name "Net-(LED_INDICATOR-PadA)") (class "Default")
      (node (ref "LED_INDICATOR") (pin "A") (pinfunction "A_A") (pintype "passive"))
      (node (ref "R5") (pin "1") (pinfunction "1_1") (pintype "passive"))
    )
    (net (code "39") (name "Net-(LED_LEFT-PadC)") (class "Default")
      (node (ref "LED_LEFT") (pin "C") (pinfunction "C_C") (pintype "passive"))
      (node (ref "R30") (pin "2") (pinfunction "2_2") (pintype "passive"))
    )
    (net (code "40") (name "Net-(LED_MIDDLE-PadC)") (class "Default")
      (node (ref "LED_MIDDLE") (pin "C") (pinfunction "C_C") (pintype "passive"))
      (node (ref "R32") (pin "2") (pinfunction "2_2") (pintype "passive"))
    )
    (net (code "41") (name "Net-(LED_RIGHT-PadC)") (class "Default")
      (node (ref "LED_RIGHT") (pin "C") (pinfunction "C_C") (pintype "passive"))
      (node (ref "R31") (pin "2") (pinfunction "2_2") (pintype "passive"))
    )
    (net (code "42") (name "Net-(N-CHANNEL-D)") (class "Default")
      (node (ref "LED_CHARGE_GREEN") (pin "C") (pinfunction "C_C") (pintype "passive"))
      (node (ref "N-CHANNEL") (pin "3") (pinfunction "D_3") (pintype "passive"))
    )
    (net (code "43") (name "Net-(NPN-PadB)") (class "Default")
      (node (ref "NPN") (pin "B") (pinfunction "B_B") (pintype "passive"))
      (node (ref "R28") (pin "2") (pinfunction "2_2") (pintype "passive"))
    )
    (net (code "44") (name "Net-(ON/OFF-S)") (class "Default")
      (node (ref "ON/OFF") (pin "3") (pinfunction "S_3") (pintype "passive"))
      (node (ref "P-CHANNEL") (pin "3") (pinfunction "D_3") (pintype "passive"))
      (node (ref "SCHOTTKY1") (pin "C") (pinfunction "C_C") (pintype "passive"))
    )
    (net (code "45") (name "Net-(OPV-+IN3)") (class "Default")
      (node (ref "C15") (pin "1") (pinfunction "1_1") (pintype "passive"))
      (node (ref "OPV") (pin "10") (pinfunction "+IN3_10") (pintype "passive"))
      (node (ref "R16") (pin "2") (pinfunction "2_2") (pintype "passive"))
    )
    (net (code "46") (name "Net-(OPV--IN3)") (class "Default")
      (node (ref "OPV") (pin "9") (pinfunction "-IN3_9") (pintype "passive"))
      (node (ref "R27") (pin "2") (pinfunction "2_2") (pintype "passive"))
      (node (ref "TRIMMER") (pin "3") (pinfunction "E_3") (pintype "passive"))
    )
    (net (code "47") (name "Net-(OPV-OUT3)") (class "Default")
      (node (ref "OPV") (pin "8") (pinfunction "OUT3_8") (pintype "passive"))
      (node (ref "R18") (pin "1") (pinfunction "1_1") (pintype "passive"))
      (node (ref "R27") (pin "1") (pinfunction "1_1") (pintype "passive"))
    )
    (net (code "48") (name "Net-(POWER_LED-PadA)") (class "Default")
      (node (ref "POWER_LED") (pin "A") (pinfunction "A_A") (pintype "passive"))
      (node (ref "R1") (pin "2") (pinfunction "2_2") (pintype "passive"))
    )
    (net (code "49") (name "Net-(R10-Pad1)") (class "Default")
      (node (ref "R10") (pin "1") (pinfunction "1_1") (pintype "passive"))
      (node (ref "R9") (pin "2") (pinfunction "2_2") (pintype "passive"))
    )
    (net (code "50") (name "Net-(R10-Pad2)") (class "Default")
      (node (ref "R10") (pin "2") (pinfunction "2_2") (pintype "passive"))
      (node (ref "R20") (pin "1") (pinfunction "1_1") (pintype "passive"))
      (node (ref "R29") (pin "1") (pinfunction "1_1") (pintype "passive"))
    )
    (net (code "51") (name "Net-(R20-Pad2)") (class "Default")
      (node (ref "R20") (pin "2") (pinfunction "2_2") (pintype "passive"))
      (node (ref "R21") (pin "1") (pinfunction "1_1") (pintype "passive"))
    )
    (net (code "52") (name "Net-(U1-EN)") (class "Default")
      (node (ref "RENABLE") (pin "2") (pinfunction "2_2") (pintype "passive"))
      (node (ref "U1") (pin "14") (pinfunction "EN_14") (pintype "input"))
    )
    (net (code "53") (name "Net-(U1-FB)") (class "Default")
      (node (ref "RFBB") (pin "2") (pinfunction "2_2") (pintype "passive"))
      (node (ref "RFBT") (pin "1") (pinfunction "1_1") (pintype "passive"))
      (node (ref "U1") (pin "5") (pinfunction "FB_5") (pintype "input"))
    )
    (net (code "54") (name "Net-(U1-L1)") (class "Default")
      (node (ref "L1") (pin "1") (pinfunction "1_1") (pintype "passive"))
      (node (ref "U1") (pin "11") (pinfunction "L1_11") (pintype "bidirectional"))
    )
    (net (code "55") (name "Net-(U1-L2)") (class "Default")
      (node (ref "L1") (pin "2") (pinfunction "2_2") (pintype "passive"))
      (node (ref "U1") (pin "9") (pinfunction "L2_9") (pintype "bidirectional"))
    )
    (net (code "56") (name "Net-(U1-PG)") (class "Default")
      (node (ref "RPGOOD") (pin "1") (pinfunction "1_1") (pintype "passive"))
      (node (ref "U1") (pin "2") (pinfunction "PG_2") (pintype "output"))
    )
    (net (code "57") (name "Net-(U1-VAUX)") (class "Default")
      (node (ref "CAUX") (pin "1") (pinfunction "1_1") (pintype "passive"))
      (node (ref "U1") (pin "3") (pinfunction "VAUX_3") (pintype "output"))
    )
    (net (code "58") (name "Net-(USB-B-D+)") (class "Default")
      (node (ref "R25") (pin "2") (pinfunction "2_2") (pintype "passive"))
      (node (ref "USB-B") (pin "3") (pinfunction "D+_3") (pintype "bidirectional"))
    )
    (net (code "59") (name "Net-(USB-B-D-)") (class "Default")
      (node (ref "R26") (pin "2") (pinfunction "2_2") (pintype "passive"))
      (node (ref "USB-B") (pin "2") (pinfunction "D-_2") (pintype "bidirectional"))
    )
    (net (code "60") (name "OSC32IN") (class "Default")
      (node (ref "C10") (pin "2") (pinfunction "2_2") (pintype "passive"))
      (node (ref "QUARTZ2") (pin "2") (pinfunction "2_2") (pintype "passive"))
      (node (ref "R37") (pin "2") (pinfunction "2_2") (pintype "passive"))
      (node (ref "STM32") (pin "3") (pinfunction "PC14-OSC32_IN_3") (pintype "bidirectional"))
    )
    (net (code "61") (name "OSC32OUT") (class "Default")
      (node (ref "C11") (pin "2") (pinfunction "2_2") (pintype "passive"))
      (node (ref "QUARTZ2") (pin "1") (pinfunction "1_1") (pintype "passive"))
      (node (ref "R37") (pin "1") (pinfunction "1_1") (pintype "passive"))
      (node (ref "STM32") (pin "4") (pinfunction "PC15-OSC32_OUT_4") (pintype "bidirectional"))
    )
    (net (code "62") (name "OSCIN") (class "Default")
      (node (ref "C8") (pin "2") (pinfunction "2_2") (pintype "passive"))
      (node (ref "QUARTZ") (pin "2") (pinfunction "2_2") (pintype "passive"))
      (node (ref "R12") (pin "2") (pinfunction "2_2") (pintype "passive"))
      (node (ref "STM32") (pin "5") (pinfunction "PD0_OSC_IN_5") (pintype "bidirectional"))
    )
    (net (code "63") (name "OSCOUT") (class "Default")
      (node (ref "C9") (pin "2") (pinfunction "2_2") (pintype "passive"))
      (node (ref "QUARTZ") (pin "1") (pinfunction "1_1") (pintype "passive"))
      (node (ref "R12") (pin "1") (pinfunction "1_1") (pintype "passive"))
      (node (ref "STM32") (pin "6") (pinfunction "PD1_OSC_OUT_6") (pintype "bidirectional"))
    )
    (net (code "64") (name "PAD") (class "Default")
      (node (ref "H-BRUECKE") (pin "8") (pinfunction "EPAD_8") (pintype "passive"))
    )
    (net (code "65") (name "PC13") (class "Default")
      (node (ref "R5") (pin "2") (pinfunction "2_2") (pintype "passive"))
      (node (ref "STM32") (pin "2") (pinfunction "PC13-TAMPER-RTC_2") (pintype "bidirectional"))
    )
    (net (code "66") (name "RESET") (class "Default")
      (node (ref "C2") (pin "1") (pinfunction "1_1") (pintype "passive"))
      (node (ref "R2") (pin "1") (pinfunction "1_1") (pintype "passive"))
      (node (ref "RESET") (pin "C") (pinfunction "NO_C") (pintype "passive"))
      (node (ref "RESET") (pin "D") (pinfunction "NO_D") (pintype "passive"))
      (node (ref "STM32") (pin "7") (pinfunction "NRST_7") (pintype "input"))
    )
    (net (code "67") (name "SIGNAL_IN") (class "Default")
      (node (ref "C15") (pin "2") (pinfunction "2_2") (pintype "passive"))
      (node (ref "JP1") (pin "2") (pinfunction "2_2") (pintype "passive"))
      (node (ref "SIGNAL_IN") (pin "TP") (pinfunction "TP_TP") (pintype "input"))
    )
    (net (code "68") (name "SIGNAL_IN_1") (class "Default")
      (node (ref "AUDIO_JACK") (pin "5") (pinfunction "TIP_2_5") (pintype "passive"))
      (node (ref "JP1") (pin "1") (pinfunction "1_1") (pintype "passive"))
    )
    (net (code "69") (name "SIGNAL_IN_2") (class "Default")
      (node (ref "AUDIO_JACK") (pin "2") (pinfunction "RING_1_2") (pintype "passive"))
      (node (ref "JP1") (pin "3") (pinfunction "3_3") (pintype "passive"))
    )
    (net (code "70") (name "SIGNAL_OPAMP") (class "Default")
      (node (ref "R18") (pin "2") (pinfunction "2_2") (pintype "passive"))
      (node (ref "SIGNAL_OPAMP") (pin "TP") (pinfunction "TP_TP") (pintype "input"))
      (node (ref "STM32") (pin "12") (pinfunction "PA2_12") (pintype "bidirectional"))
    )
    (net (code "71") (name "SWDCLK") (class "Default")
      (node (ref "STM32") (pin "37") (pinfunction "PA14_37") (pintype "bidirectional"))
      (node (ref "ST_LINK") (pin "2") (pinfunction "2_2") (pintype "passive"))
    )
    (net (code "72") (name "SWDIO") (class "Default")
      (node (ref "STM32") (pin "34") (pinfunction "PA13_34") (pintype "bidirectional"))
      (node (ref "ST_LINK") (pin "3") (pinfunction "3_3") (pintype "passive"))
    )
    (net (code "73") (name "USB+") (class "Default")
      (node (ref "D4") (pin "2") (pinfunction "2_2") (pintype "passive"))
      (node (ref "R13") (pin "1") (pinfunction "1_1") (pintype "passive"))
      (node (ref "R25") (pin "1") (pinfunction "1_1") (pintype "passive"))
      (node (ref "STM32") (pin "33") (pinfunction "PA12_33") (pintype "bidirectional"))
    )
    (net (code "74") (name "USB-") (class "Default")
      (node (ref "D3") (pin "2") (pinfunction "2_2") (pintype "passive"))
      (node (ref "R26") (pin "1") (pinfunction "1_1") (pintype "passive"))
      (node (ref "STM32") (pin "32") (pinfunction "PA11_32") (pintype "bidirectional"))
    )
    (net (code "75") (name "VBAT") (class "Default")
      (node (ref "BATTERIE1") (pin "2") (pinfunction "S_2") (pintype "passive"))
      (node (ref "BATTERYCHARGER") (pin "3") (pinfunction "BAT_3") (pintype "bidirectional"))
      (node (ref "C_H-BRIDGE") (pin "+") (pinfunction "+_+") (pintype "passive"))
      (node (ref "H-BRUECKE") (pin "1") (pinfunction "VREF_1") (pintype "power_in"))
      (node (ref "H-BRUECKE") (pin "7") (pinfunction "VCC_7") (pintype "power_in"))
      (node (ref "P-CHANNEL") (pin "2") (pinfunction "S_2") (pintype "passive"))
      (node (ref "R21") (pin "2") (pinfunction "2_2") (pintype "passive"))
      (node (ref "VBAT") (pin "TP") (pinfunction "TP_TP") (pintype "input"))
    )
    (net (code "76") (name "VBUS") (class "Default")
      (node (ref "BATTERYCHARGER") (pin "4") (pinfunction "VCC_4") (pintype "bidirectional"))
      (node (ref "C12") (pin "1") (pinfunction "1_1") (pintype "passive"))
      (node (ref "D2") (pin "2") (pinfunction "2_2") (pintype "passive"))
      (node (ref "P-CHANNEL") (pin "1") (pinfunction "G_1") (pintype "passive"))
      (node (ref "R11") (pin "2") (pinfunction "2_2") (pintype "passive"))
      (node (ref "R7") (pin "1") (pinfunction "1_1") (pintype "passive"))
      (node (ref "R8") (pin "1") (pinfunction "1_1") (pintype "passive"))
      (node (ref "SCHOTTKY1") (pin "A") (pinfunction "A_A") (pintype "passive"))
      (node (ref "USB-B") (pin "1") (pinfunction "VCC_1") (pintype "power_in"))
      (node (ref "VBUS") (pin "TP") (pinfunction "TP_TP") (pintype "input"))
    )
    (net (code "77") (name "VIN") (class "Default")
      (node (ref "CIN") (pin "1") (pinfunction "1_1") (pintype "passive"))
      (node (ref "ON/OFF") (pin "2") (pinfunction "P_2") (pintype "passive"))
      (node (ref "RENABLE") (pin "1") (pinfunction "1_1") (pintype "passive"))
      (node (ref "U1") (pin "1") (pinfunction "PS/SYNC_1") (pintype "input"))
      (node (ref "U1") (pin "12_13") (pinfunction "VIN_12_13") (pintype "input"))
    )
    (net (code "78") (name "unconnected-(ON/OFF-O-Pad1)") (class "Default")
      (node (ref "ON/OFF") (pin "1") (pinfunction "O_1") (pintype "passive"))
    )
    (net (code "79") (name "unconnected-(OPV-+IN1-Pad3)") (class "Default")
      (node (ref "OPV") (pin "3") (pinfunction "+IN1_3") (pintype "bidirectional"))
    )
    (net (code "80") (name "unconnected-(OPV-+IN2-Pad5)") (class "Default")
      (node (ref "OPV") (pin "5") (pinfunction "+IN2_5") (pintype "passive"))
    )
    (net (code "81") (name "unconnected-(OPV-+IN4-Pad12)") (class "Default")
      (node (ref "OPV") (pin "12") (pinfunction "+IN4_12") (pintype "bidirectional"))
    )
    (net (code "82") (name "unconnected-(OPV--IN1-Pad2)") (class "Default")
      (node (ref "OPV") (pin "2") (pinfunction "-IN1_2") (pintype "input"))
    )
    (net (code "83") (name "unconnected-(OPV--IN2-Pad6)") (class "Default")
      (node (ref "OPV") (pin "6") (pinfunction "-IN2_6") (pintype "passive"))
    )
    (net (code "84") (name "unconnected-(OPV--IN4-Pad13)") (class "Default")
      (node (ref "OPV") (pin "13") (pinfunction "-IN4_13") (pintype "bidirectional"))
    )
    (net (code "85") (name "unconnected-(OPV-OUT1-Pad1)") (class "Default")
      (node (ref "OPV") (pin "1") (pinfunction "OUT1_1") (pintype "input"))
    )
    (net (code "86") (name "unconnected-(OPV-OUT2-Pad7)") (class "Default")
      (node (ref "OPV") (pin "7") (pinfunction "OUT2_7") (pintype "passive"))
    )
    (net (code "87") (name "unconnected-(OPV-OUT4-Pad14)") (class "Default")
      (node (ref "OPV") (pin "14") (pinfunction "OUT4_14") (pintype "output"))
    )
    (net (code "88") (name "unconnected-(STM32-PA0_WKUP-Pad10)") (class "Default")
      (node (ref "STM32") (pin "10") (pinfunction "PA0_WKUP_10") (pintype "bidirectional"))
    )
    (net (code "89") (name "unconnected-(STM32-PA1-Pad11)") (class "Default")
      (node (ref "STM32") (pin "11") (pinfunction "PA1_11") (pintype "bidirectional"))
    )
    (net (code "90") (name "unconnected-(STM32-PA3-Pad13)") (class "Default")
      (node (ref "STM32") (pin "13") (pinfunction "PA3_13") (pintype "bidirectional"))
    )
    (net (code "91") (name "unconnected-(STM32-PA4-Pad14)") (class "Default")
      (node (ref "STM32") (pin "14") (pinfunction "PA4_14") (pintype "bidirectional"))
    )
    (net (code "92") (name "unconnected-(STM32-PA5-Pad15)") (class "Default")
      (node (ref "STM32") (pin "15") (pinfunction "PA5_15") (pintype "bidirectional"))
    )
    (net (code "93") (name "unconnected-(STM32-PA7-Pad17)") (class "Default")
      (node (ref "STM32") (pin "17") (pinfunction "PA7_17") (pintype "bidirectional"))
    )
    (net (code "94") (name "unconnected-(STM32-PB2-Pad20)") (class "Default")
      (node (ref "STM32") (pin "20") (pinfunction "PB2_20") (pintype "bidirectional"))
    )
    (net (code "95") (name "unconnected-(STM32-PB9-Pad46)") (class "Default")
      (node (ref "STM32") (pin "46") (pinfunction "PB9_46") (pintype "bidirectional"))
    )
    (net (code "96") (name "unconnected-(STM32-PB10-Pad21)") (class "Default")
      (node (ref "STM32") (pin "21") (pinfunction "PB10_21") (pintype "bidirectional"))
    )
    (net (code "97") (name "unconnected-(STM32-PB11-Pad22)") (class "Default")
      (node (ref "STM32") (pin "22") (pinfunction "PB11_22") (pintype "bidirectional"))
    )
    (net (code "98") (name "unconnected-(STM32-PB12-Pad25)") (class "Default")
      (node (ref "STM32") (pin "25") (pinfunction "PB12_25") (pintype "bidirectional"))
    )
  )
)
